# SuperBC.net
KiCad netlist of a schematic drawn in Altium Designer
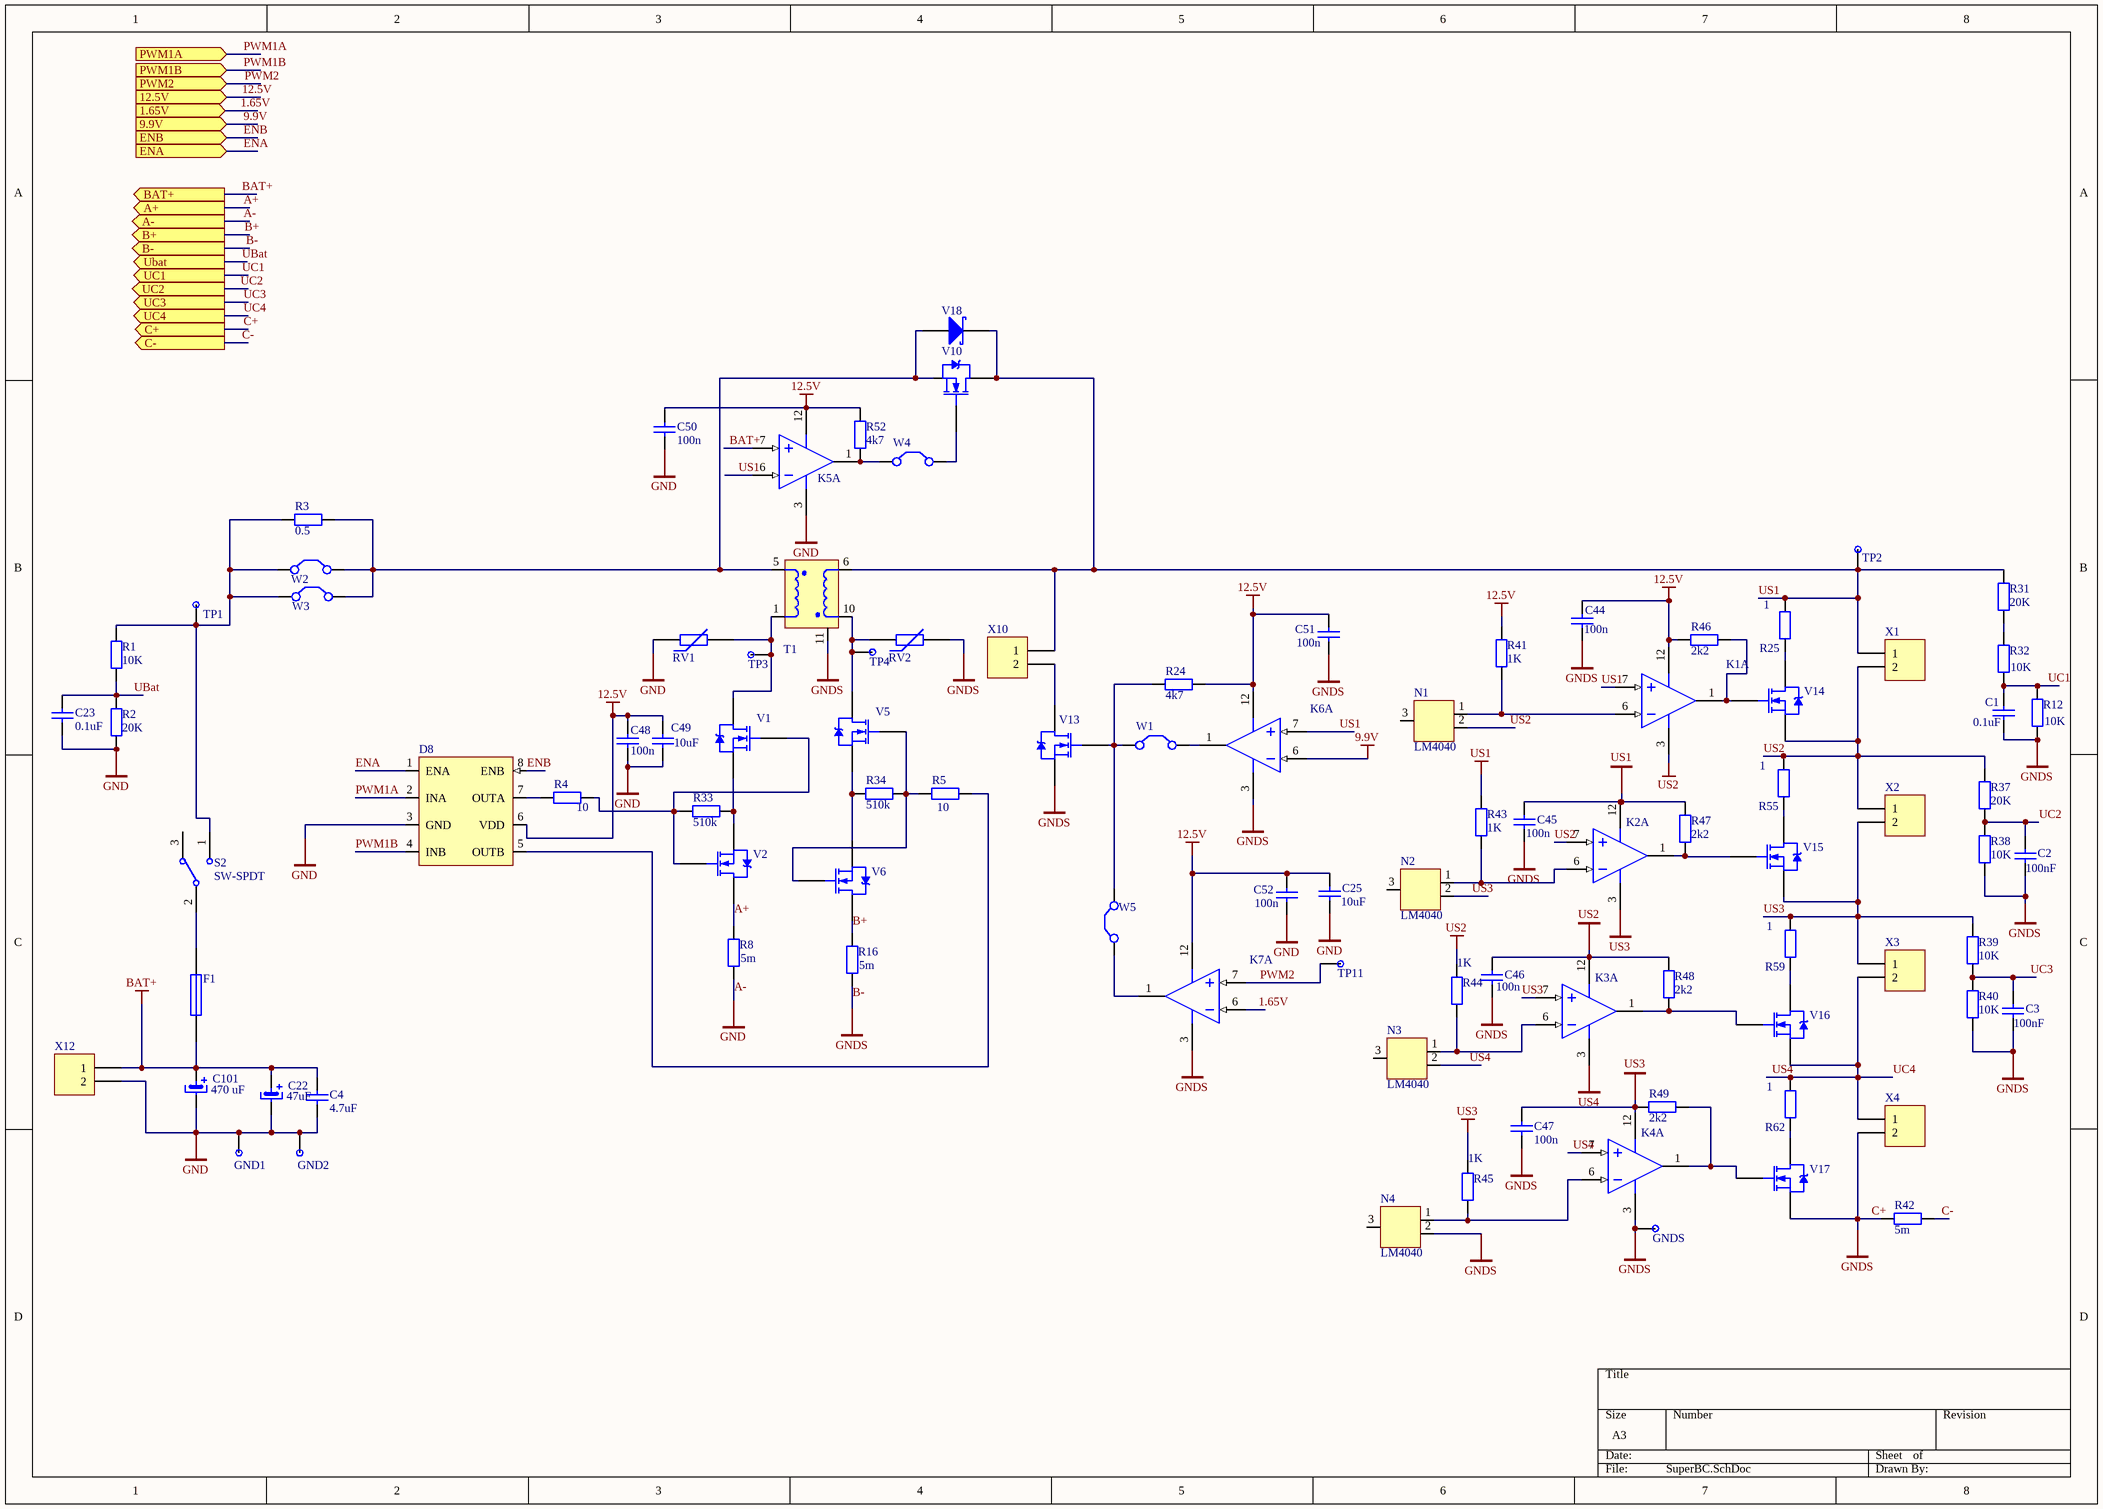
[diagram p0: SuperBC.SchDoc]

(export (version "E")
  (design (tool "Eeschema 10.0.6"))
  (components
    (comp (ref "C1")
      (value "0.1uF")
      (footprint "C1210_L")
      (description "Capacitor")
      (libsource (lib "Miscellaneous Devices") (part "Cap"))
    )
    (comp (ref "C2")
      (value "100nF")
      (footprint "C1210_L")
      (description "Capacitor")
      (fields (field (name "Comment") "0.1uF"))
      (libsource (lib "Miscellaneous Devices") (part "Cap"))
    )
    (comp (ref "C3")
      (value "100nF")
      (footprint "C1210_L")
      (description "Capacitor")
      (fields (field (name "Comment") "0.1uF"))
      (libsource (lib "Miscellaneous Devices") (part "Cap"))
    )
    (comp (ref "C4")
      (value "4.7uF")
      (footprint "C0805")
      (description "Capacitor")
      (libsource (lib "Miscellaneous Devices") (part "Cap"))
    )
    (comp (ref "C22")
      (value "47uF")
      (footprint "SMD_CAP_RAD_8X10.2")
      (libsource (lib "komponente") (part "elko"))
    )
    (comp (ref "C23")
      (value "0.1uF")
      (footprint "C1210_L")
      (description "Capacitor")
      (libsource (lib "Miscellaneous Devices") (part "Cap"))
    )
    (comp (ref "C25")
      (value "10uF")
      (footprint "C1210_L")
      (description "Capacitor")
      (libsource (lib "Miscellaneous Devices") (part "Cap"))
    )
    (comp (ref "C44")
      (value "100n")
      (footprint "C0805")
      (description "Capacitor")
      (libsource (lib "Miscellaneous Devices") (part "Cap"))
    )
    (comp (ref "C45")
      (value "100n")
      (footprint "C0805")
      (description "Capacitor")
      (libsource (lib "Miscellaneous Devices") (part "Cap"))
    )
    (comp (ref "C46")
      (value "100n")
      (footprint "C0805")
      (description "Capacitor")
      (libsource (lib "Miscellaneous Devices") (part "Cap"))
    )
    (comp (ref "C47")
      (value "100n")
      (footprint "C0805")
      (description "Capacitor")
      (libsource (lib "Miscellaneous Devices") (part "Cap"))
    )
    (comp (ref "C48")
      (value "100n")
      (footprint "C0805")
      (description "Capacitor")
      (libsource (lib "Miscellaneous Devices") (part "Cap"))
    )
    (comp (ref "C49")
      (value "10uF")
      (footprint "C1210_L")
      (description "Capacitor")
      (libsource (lib "Miscellaneous Devices") (part "Cap"))
    )
    (comp (ref "C50")
      (value "100n")
      (footprint "C0805")
      (description "Capacitor")
      (libsource (lib "Miscellaneous Devices") (part "Cap"))
    )
    (comp (ref "C51")
      (value "100n")
      (footprint "C0805")
      (description "Capacitor")
      (libsource (lib "Miscellaneous Devices") (part "Cap"))
    )
    (comp (ref "C52")
      (value "100n")
      (footprint "C0805")
      (description "Capacitor")
      (libsource (lib "Miscellaneous Devices") (part "Cap"))
    )
    (comp (ref "C101")
      (value "470 uF")
      (footprint "SMD_CAP_RAD_8X10.2")
      (libsource (lib "komponente") (part "elko"))
    )
    (comp (ref "D8")
      (value "driver_mosfet")
      (footprint "SOIC8")
      (libsource (lib "komponente") (part "driver_mosfet"))
    )
    (comp (ref "F1")
      (value "Fuse 1")
      (footprint "C1206")
      (description "Fuse")
      (libsource (lib "Miscellaneous Devices") (part "Fuse 1"))
    )
    (comp (ref "GND1") (value "*") (libsource (lib "komponente") (part "testpoint")))
    (comp (ref "GND2") (value "*") (libsource (lib "komponente") (part "testpoint")))
    (comp (ref "GNDS") (value "*") (libsource (lib "komponente") (part "testpoint")))
    (comp (ref "K1")
      (value "TLC3704QJ")
      (footprint "SOT-23")
      (description "Low Power Quad Differential Comparator")
      (libsource (lib "TI Analog Comparator") (part "LP2901D"))
    )
    (comp (ref "K2")
      (value "TLC3704QJ")
      (footprint "SOT-23")
      (description "Low Power Quad Differential Comparator")
      (libsource (lib "TI Analog Comparator") (part "LP2901D"))
    )
    (comp (ref "K3")
      (value "TLC3704QJ")
      (footprint "SOT-23")
      (description "Low Power Quad Differential Comparator")
      (libsource (lib "TI Analog Comparator") (part "LP2901D"))
    )
    (comp (ref "K4")
      (value "TLC3704QJ")
      (footprint "SOT-23")
      (description "Low Power Quad Differential Comparator")
      (libsource (lib "TI Analog Comparator") (part "LP2901D"))
    )
    (comp (ref "K5")
      (value "NCS2200")
      (footprint "SOT-23")
      (description "Low Power Quad Differential Comparator")
      (libsource (lib "TI Analog Comparator") (part "LP2901D"))
    )
    (comp (ref "K6")
      (value "TLC3704QJ")
      (footprint "SOT-23")
      (description "Low Power Quad Differential Comparator")
      (libsource (lib "TI Analog Comparator") (part "LP2901D"))
    )
    (comp (ref "K7")
      (value "TLC3704QJ")
      (footprint "SOT-23")
      (description "Low Power Quad Differential Comparator")
      (libsource (lib "TI Analog Comparator") (part "LP2901D"))
    )
    (comp (ref "N1")
      (value "LM4040")
      (footprint "SOT-23-ref_chip")
      (libsource (lib "komponente") (part "referentni chip"))
    )
    (comp (ref "N2")
      (value "LM4040")
      (footprint "SOT-23-ref_chip")
      (libsource (lib "komponente") (part "referentni chip"))
    )
    (comp (ref "N3")
      (value "LM4040")
      (footprint "SOT-23-ref_chip")
      (libsource (lib "komponente") (part "referentni chip"))
    )
    (comp (ref "N4")
      (value "LM4040")
      (footprint "SOT-23-ref_chip")
      (libsource (lib "komponente") (part "referentni chip"))
    )
    (comp (ref "R1")
      (value "10K")
      (footprint "C1210_L")
      (description "Resistor")
      (libsource (lib "Miscellaneous Devices") (part "Res2"))
    )
    (comp (ref "R2")
      (value "20K")
      (footprint "C1210_L")
      (description "Resistor")
      (libsource (lib "Miscellaneous Devices") (part "Res2"))
    )
    (comp (ref "R3")
      (value "0.5")
      (footprint "C2512")
      (description "Resistor")
      (libsource (lib "") (part "Res2_1"))
    )
    (comp (ref "R4")
      (value "10")
      (footprint "C0805")
      (description "Resistor")
      (libsource (lib "") (part "Res2_1"))
    )
    (comp (ref "R5")
      (value "10")
      (footprint "C0805")
      (description "Resistor")
      (libsource (lib "") (part "Res2_1"))
    )
    (comp (ref "R8")
      (value "5m")
      (footprint "otpornik R8, R16")
      (description "Resistor")
      (libsource (lib "Miscellaneous Devices") (part "Res2"))
    )
    (comp (ref "R12")
      (value "10K")
      (footprint "C1210_L")
      (description "Resistor")
      (libsource (lib "") (part "Res2_1"))
    )
    (comp (ref "R16")
      (value "5m")
      (footprint "otpornik R8, R16")
      (description "Resistor")
      (libsource (lib "Miscellaneous Devices") (part "Res2"))
    )
    (comp (ref "R24")
      (value "4k7")
      (footprint "C1206")
      (description "Resistor")
      (libsource (lib "") (part "Res2_1"))
    )
    (comp (ref "R25")
      (value "1")
      (footprint "F za 7W otpornik")
      (description "Resistor")
      (libsource (lib "Miscellaneous Devices") (part "Res2"))
    )
    (comp (ref "R31")
      (value "20K")
      (footprint "C1210_L")
      (description "Resistor")
      (libsource (lib "Miscellaneous Devices") (part "Res2"))
    )
    (comp (ref "R32")
      (value "10K")
      (footprint "C1210_L")
      (description "Resistor")
      (libsource (lib "") (part "Res2_1"))
    )
    (comp (ref "R33")
      (value "510k")
      (footprint "C1210_L")
      (description "Resistor")
      (libsource (lib "") (part "Res2_1"))
    )
    (comp (ref "R34")
      (value "510k")
      (footprint "C1210_L")
      (description "Resistor")
      (libsource (lib "") (part "Res2_1"))
    )
    (comp (ref "R37")
      (value "20K")
      (footprint "C1210_L")
      (description "Resistor")
      (libsource (lib "Miscellaneous Devices") (part "Res2"))
    )
    (comp (ref "R38")
      (value "10K")
      (footprint "C1210_L")
      (description "Resistor")
      (libsource (lib "Miscellaneous Devices") (part "Res2"))
    )
    (comp (ref "R39")
      (value "10K")
      (footprint "C1210_L")
      (description "Resistor")
      (libsource (lib "Miscellaneous Devices") (part "Res2"))
    )
    (comp (ref "R40")
      (value "10K")
      (footprint "C1210_L")
      (description "Resistor")
      (libsource (lib "Miscellaneous Devices") (part "Res2"))
    )
    (comp (ref "R41")
      (value "1K")
      (footprint "C1210_L")
      (description "Resistor")
      (libsource (lib "Miscellaneous Devices") (part "Res2"))
    )
    (comp (ref "R42")
      (value "5m")
      (footprint "otpornik R8, R16")
      (description "Resistor")
      (libsource (lib "") (part "Res2_2"))
    )
    (comp (ref "R43")
      (value "1K")
      (footprint "C1210_L")
      (description "Resistor")
      (libsource (lib "Miscellaneous Devices") (part "Res2"))
    )
    (comp (ref "R44")
      (value "1K")
      (footprint "C1210_L")
      (description "Resistor")
      (libsource (lib "Miscellaneous Devices") (part "Res2"))
    )
    (comp (ref "R45")
      (value "1K")
      (footprint "C1210_L")
      (description "Resistor")
      (libsource (lib "Miscellaneous Devices") (part "Res2"))
    )
    (comp (ref "R46")
      (value "2k2")
      (footprint "C1210_L")
      (description "Resistor")
      (libsource (lib "") (part "Res2_1"))
    )
    (comp (ref "R47")
      (value "2k2")
      (footprint "C1210_L")
      (description "Resistor")
      (libsource (lib "Miscellaneous Devices") (part "Res2"))
    )
    (comp (ref "R48")
      (value "2k2")
      (footprint "C1210_L")
      (description "Resistor")
      (libsource (lib "Miscellaneous Devices") (part "Res2"))
    )
    (comp (ref "R49")
      (value "2k2")
      (footprint "C1210_L")
      (description "Resistor")
      (libsource (lib "") (part "Res2_2"))
    )
    (comp (ref "R52")
      (value "4k7")
      (footprint "C1206")
      (description "Resistor")
      (libsource (lib "Miscellaneous Devices") (part "Res2"))
    )
    (comp (ref "R55")
      (value "1")
      (footprint "F za 7W otpornik")
      (description "Resistor")
      (libsource (lib "Miscellaneous Devices") (part "Res2"))
    )
    (comp (ref "R59")
      (value "1")
      (footprint "F za 7W otpornik")
      (description "Resistor")
      (libsource (lib "Miscellaneous Devices") (part "Res2"))
    )
    (comp (ref "R62")
      (value "1")
      (footprint "F za 7W otpornik")
      (description "Resistor")
      (libsource (lib "Miscellaneous Devices") (part "Res2"))
    )
    (comp (ref "RV1")
      (value "Res Varistor")
      (footprint "C1210_L")
      (description "Varistor (Voltage-Sensitive Resistor)")
      (libsource (lib "Miscellaneous Devices") (part "Res Varistor"))
    )
    (comp (ref "RV2")
      (value "Res Varistor")
      (footprint "C1210_L")
      (description "Varistor (Voltage-Sensitive Resistor)")
      (libsource (lib "Miscellaneous Devices") (part "Res Varistor"))
    )
    (comp (ref "S2")
      (value "SW-SPDT")
      (footprint "toggle_switch")
      (description "SPDT Subminiature Toggle Switch, Right Angle Mounting, Vertical Actuation")
      (libsource (lib "Miscellaneous Devices") (part "SW-SPDT"))
    )
    (comp (ref "T1")
      (value "transformator")
      (footprint "F za transformator")
      (libsource (lib "komponente") (part "transformator"))
    )
    (comp (ref "TP1") (value "*") (libsource (lib "komponente") (part "testpoint")))
    (comp (ref "TP2") (value "*") (libsource (lib "komponente") (part "testpoint")))
    (comp (ref "TP3") (value "*") (libsource (lib "komponente") (part "testpoint")))
    (comp (ref "TP4") (value "*") (libsource (lib "komponente") (part "testpoint")))
    (comp (ref "TP11") (value "*") (libsource (lib "komponente") (part "testpoint")))
    (comp (ref "V1")
      (value "NMOS-2")
      (footprint "SO-8L single_f")
      (description "N-Channel Power MOSFET")
      (libsource (lib "") (part "NMOS-2_1"))
    )
    (comp (ref "V2")
      (value "NMOS-2")
      (footprint "SO-8L single_f")
      (description "N-Channel Power MOSFET")
      (libsource (lib "") (part "NMOS-2_1"))
    )
    (comp (ref "V5")
      (value "NMOS-2")
      (footprint "SO-8L single_f")
      (description "N-Channel Power MOSFET")
      (libsource (lib "") (part "NMOS-2_1"))
    )
    (comp (ref "V6")
      (value "NMOS-2")
      (footprint "SO-8L single_f")
      (description "N-Channel Power MOSFET")
      (libsource (lib "") (part "NMOS-2_1"))
    )
    (comp (ref "V10")
      (value "MOSFET-N")
      (footprint "TO-252-3")
      (description "N-Channel Power MOSFET")
      (libsource (lib "Miscellaneous Devices") (part "NMOS-2"))
    )
    (comp (ref "V13")
      (value "MOSFET-N")
      (footprint "TO-252-3")
      (description "N-Channel Power MOSFET")
      (libsource (lib "Miscellaneous Devices") (part "NMOS-2"))
    )
    (comp (ref "V14")
      (value "NMOS-2")
      (footprint "SO-8L single_f")
      (description "N-Channel Power MOSFET")
      (libsource (lib "") (part "NMOS-2_1"))
    )
    (comp (ref "V15")
      (value "NMOS-2")
      (footprint "SO-8L single_f")
      (description "N-Channel Power MOSFET")
      (libsource (lib "") (part "NMOS-2_1"))
    )
    (comp (ref "V16")
      (value "NMOS-2")
      (footprint "SO-8L single_f")
      (description "N-Channel Power MOSFET")
      (libsource (lib "") (part "NMOS-2_1"))
    )
    (comp (ref "V17")
      (value "NMOS-2")
      (footprint "SO-8L single_f")
      (description "N-Channel Power MOSFET")
      (libsource (lib "") (part "NMOS-2_1"))
    )
    (comp (ref "V18")
      (value "Schottky Diode")
      (footprint "TO-220-AB")
      (libsource (lib "Miscellaneous Devices") (part "D Schottky"))
    )
    (comp (ref "W1")
      (value "Jumper")
      (footprint "HDR1X2")
      (description "Jumper Wire")
      (libsource (lib "Miscellaneous Devices") (part "Jumper"))
    )
    (comp (ref "W2")
      (value "Jumper 4.3A")
      (footprint "HDR1X2")
      (description "Jumper Wire")
      (libsource (lib "Miscellaneous Devices") (part "Jumper"))
    )
    (comp (ref "W3")
      (value "Jumper 4.3A")
      (footprint "HDR1X2")
      (description "Jumper Wire")
      (libsource (lib "Miscellaneous Devices") (part "Jumper"))
    )
    (comp (ref "W4")
      (value "Jumper")
      (footprint "HDR1X2")
      (description "Jumper Wire")
      (libsource (lib "Miscellaneous Devices") (part "Jumper"))
    )
    (comp (ref "W5")
      (value "Jumper")
      (footprint "HDR1X2")
      (description "Jumper Wire")
      (libsource (lib "Miscellaneous Devices") (part "Jumper"))
    )
    (comp (ref "X1")
      (value "Header 2")
      (footprint "F Header 1x2")
      (description "Header, 2-Pin")
      (libsource (lib "") (part "Header 2_1"))
    )
    (comp (ref "X2")
      (value "Header 2")
      (footprint "F Header 1x2")
      (description "Header, 2-Pin")
      (libsource (lib "") (part "Header 2_1"))
    )
    (comp (ref "X3")
      (value "Header 2")
      (footprint "F Header 1x2")
      (description "Header, 2-Pin")
      (libsource (lib "") (part "Header 2_1"))
    )
    (comp (ref "X4")
      (value "Header 2")
      (footprint "F Header 1x2")
      (description "Header, 2-Pin")
      (libsource (lib "") (part "Header 2_1"))
    )
    (comp (ref "X10")
      (value "Header 2")
      (footprint "F Header 1x2")
      (description "Header, 2-Pin")
      (libsource (lib "Miscellaneous Connectors") (part "Header 2"))
    )
    (comp (ref "X12")
      (value "Header 2")
      (footprint "F Header 1x2")
      (description "Header, 2-Pin")
      (libsource (lib "Miscellaneous Connectors") (part "Header 2"))
    )
  )
  (nets
    (net (code "1") (name "/1.65V") (class "Default")
      (node (ref "K7") (pin "6") (pinfunction "IN-_6") (pintype "input"))
    )
    (net (code "3") (name "/A+") (class "Default")
      (node (ref "R8") (pin "2") (pinfunction "2_2") (pintype "passive"))
      (node (ref "V2") (pin "2") (pinfunction "D_2") (pintype "passive"))
    )
    (net (code "4") (name "/B+") (class "Default")
      (node (ref "R16") (pin "2") (pinfunction "2_2") (pintype "passive"))
      (node (ref "V6") (pin "2") (pinfunction "D_2") (pintype "passive"))
    )
    (net (code "5") (name "/C-") (class "Default")
      (node (ref "R42") (pin "1") (pinfunction "1_1") (pintype "passive"))
    )
    (net (code "6") (name "/ENA") (class "Default")
      (node (ref "D8") (pin "1") (pinfunction "ENA_1") (pintype "bidirectional"))
    )
    (net (code "7") (name "/ENB") (class "Default")
      (node (ref "D8") (pin "8") (pinfunction "ENB_8") (pintype "input"))
    )
    (net (code "8") (name "/PWM1A") (class "Default")
      (node (ref "D8") (pin "2") (pinfunction "INA_2") (pintype "passive"))
    )
    (net (code "9") (name "/PWM1B") (class "Default")
      (node (ref "D8") (pin "4") (pinfunction "INB_4") (pintype "passive"))
    )
    (net (code "10") (name "/PWM2") (class "Default")
      (node (ref "K7") (pin "7") (pinfunction "IN+_7") (pintype "input"))
      (node (ref "TP11") (pin "1") (pinfunction "1_1") (pintype "passive"))
    )
    (net (code "11") (name "/UBat") (class "Default")
      (node (ref "C23") (pin "2") (pinfunction "2_2") (pintype "passive"))
      (node (ref "R1") (pin "1") (pinfunction "1_1") (pintype "passive"))
      (node (ref "R2") (pin "2") (pinfunction "2_2") (pintype "passive"))
    )
    (net (code "12") (name "/UC1") (class "Default")
      (node (ref "C1") (pin "2") (pinfunction "2_2") (pintype "passive"))
      (node (ref "R12") (pin "2") (pinfunction "2_2") (pintype "passive"))
      (node (ref "R32") (pin "1") (pinfunction "1_1") (pintype "passive"))
    )
    (net (code "13") (name "/UC2") (class "Default")
      (node (ref "C2") (pin "2") (pinfunction "2_2") (pintype "passive"))
      (node (ref "R37") (pin "1") (pinfunction "1_1") (pintype "passive"))
      (node (ref "R38") (pin "2") (pinfunction "2_2") (pintype "passive"))
    )
    (net (code "14") (name "/UC3") (class "Default")
      (node (ref "C3") (pin "2") (pinfunction "2_2") (pintype "passive"))
      (node (ref "R39") (pin "1") (pinfunction "1_1") (pintype "passive"))
      (node (ref "R40") (pin "2") (pinfunction "2_2") (pintype "passive"))
    )
    (net (code "15") (name "9.9V") (class "Default")
      (node (ref "K6") (pin "6") (pinfunction "IN-_6") (pintype "input"))
    )
    (net (code "16") (name "12.5V") (class "Default")
      (node (ref "C25") (pin "2") (pinfunction "2_2") (pintype "passive"))
      (node (ref "C44") (pin "2") (pinfunction "2_2") (pintype "passive"))
      (node (ref "C48") (pin "2") (pinfunction "2_2") (pintype "passive"))
      (node (ref "C49") (pin "2") (pinfunction "2_2") (pintype "passive"))
      (node (ref "C50") (pin "2") (pinfunction "2_2") (pintype "passive"))
      (node (ref "C51") (pin "2") (pinfunction "2_2") (pintype "passive"))
      (node (ref "C52") (pin "2") (pinfunction "2_2") (pintype "passive"))
      (node (ref "D8") (pin "6") (pinfunction "VDD_6") (pintype "passive"))
      (node (ref "K1") (pin "12") (pinfunction "V-_12") (pintype "passive"))
      (node (ref "K5") (pin "12") (pinfunction "V-_12") (pintype "passive"))
      (node (ref "K6") (pin "12") (pinfunction "V-_12") (pintype "passive"))
      (node (ref "K7") (pin "12") (pinfunction "V-_12") (pintype "passive"))
      (node (ref "R24") (pin "2") (pinfunction "2_2") (pintype "passive"))
      (node (ref "R41") (pin "2") (pinfunction "2_2") (pintype "passive"))
      (node (ref "R46") (pin "1") (pinfunction "1_1") (pintype "passive"))
      (node (ref "R52") (pin "2") (pinfunction "2_2") (pintype "passive"))
    )
    (net (code "17") (name "BAT+") (class "Default")
      (node (ref "C101") (pin "1") (pintype "passive"))
      (node (ref "C22") (pin "1") (pintype "passive"))
      (node (ref "C4") (pin "2") (pinfunction "2_2") (pintype "passive"))
      (node (ref "F1") (pin "1") (pinfunction "1_1") (pintype "passive"))
      (node (ref "K5") (pin "7") (pinfunction "IN+_7") (pintype "input"))
      (node (ref "X12") (pin "1") (pinfunction "1_1") (pintype "passive"))
    )
    (net (code "18") (name "GND") (class "Default")
      (node (ref "C101") (pin "2") (pinfunction "2_2") (pintype "passive"))
      (node (ref "C22") (pin "2") (pinfunction "2_2") (pintype "passive"))
      (node (ref "C23") (pin "1") (pinfunction "1_1") (pintype "passive"))
      (node (ref "C25") (pin "1") (pinfunction "1_1") (pintype "passive"))
      (node (ref "C4") (pin "1") (pinfunction "1_1") (pintype "passive"))
      (node (ref "C48") (pin "1") (pinfunction "1_1") (pintype "passive"))
      (node (ref "C49") (pin "1") (pinfunction "1_1") (pintype "passive"))
      (node (ref "C50") (pin "1") (pinfunction "1_1") (pintype "passive"))
      (node (ref "C52") (pin "1") (pinfunction "1_1") (pintype "passive"))
      (node (ref "D8") (pin "3") (pinfunction "GND_3") (pintype "bidirectional"))
      (node (ref "GND1") (pin "1") (pinfunction "1_1") (pintype "passive"))
      (node (ref "GND2") (pin "1") (pinfunction "1_1") (pintype "passive"))
      (node (ref "K5") (pin "3") (pinfunction "V+_3") (pintype "passive"))
      (node (ref "R2") (pin "1") (pinfunction "1_1") (pintype "passive"))
      (node (ref "R8") (pin "1") (pinfunction "1_1") (pintype "passive"))
      (node (ref "RV1") (pin "1") (pinfunction "1_1") (pintype "passive"))
      (node (ref "X12") (pin "2") (pinfunction "2_2") (pintype "passive"))
    )
    (net (code "19") (name "GNDS") (class "Default")
      (node (ref "C1") (pin "1") (pinfunction "1_1") (pintype "passive"))
      (node (ref "C2") (pin "1") (pinfunction "1_1") (pintype "passive"))
      (node (ref "C3") (pin "1") (pinfunction "1_1") (pintype "passive"))
      (node (ref "C44") (pin "1") (pinfunction "1_1") (pintype "passive"))
      (node (ref "C45") (pin "1") (pinfunction "1_1") (pintype "passive"))
      (node (ref "C46") (pin "1") (pinfunction "1_1") (pintype "passive"))
      (node (ref "C47") (pin "1") (pinfunction "1_1") (pintype "passive"))
      (node (ref "C51") (pin "1") (pinfunction "1_1") (pintype "passive"))
      (node (ref "GNDS") (pin "1") (pinfunction "1_1") (pintype "passive"))
      (node (ref "K4") (pin "3") (pinfunction "V+_3") (pintype "passive"))
      (node (ref "K6") (pin "3") (pinfunction "V+_3") (pintype "passive"))
      (node (ref "K7") (pin "3") (pinfunction "V+_3") (pintype "passive"))
      (node (ref "N4") (pin "2") (pinfunction "2_2") (pintype "passive"))
      (node (ref "R12") (pin "1") (pinfunction "1_1") (pintype "passive"))
      (node (ref "R16") (pin "1") (pinfunction "1_1") (pintype "passive"))
      (node (ref "R38") (pin "1") (pinfunction "1_1") (pintype "passive"))
      (node (ref "R40") (pin "1") (pinfunction "1_1") (pintype "passive"))
      (node (ref "R42") (pin "2") (pinfunction "2_2") (pintype "passive"))
      (node (ref "RV2") (pin "2") (pinfunction "2_2") (pintype "passive"))
      (node (ref "T1") (pin "11") (pinfunction "11_11") (pintype "passive"))
      (node (ref "V13") (pin "2") (pinfunction "S_2") (pintype "passive"))
      (node (ref "V17") (pin "3") (pinfunction "S_3") (pintype "passive"))
      (node (ref "X4") (pin "2") (pinfunction "2_2") (pintype "passive"))
    )
    (net (code "20") (name "Net-(D8-OUTA)") (class "Default")
      (node (ref "D8") (pin "7") (pinfunction "OUTA_7") (pintype "passive"))
      (node (ref "R4") (pin "1") (pinfunction "1_1") (pintype "passive"))
    )
    (net (code "21") (name "Net-(D8-OUTB)") (class "Default")
      (node (ref "D8") (pin "5") (pinfunction "OUTB_5") (pintype "passive"))
      (node (ref "R5") (pin "2") (pinfunction "2_2") (pintype "passive"))
    )
    (net (code "22") (name "Net-(F1-Pad2)") (class "Default")
      (node (ref "F1") (pin "2") (pinfunction "2_2") (pintype "passive"))
      (node (ref "S2") (pin "2") (pinfunction "2_2") (pintype "passive"))
    )
    (net (code "23") (name "Net-(K1A-IN-)") (class "Default")
      (node (ref "K1") (pin "6") (pinfunction "IN-_6") (pintype "input"))
      (node (ref "N1") (pin "1") (pinfunction "1_1") (pintype "bidirectional"))
      (node (ref "R41") (pin "1") (pinfunction "1_1") (pintype "passive"))
    )
    (net (code "24") (name "Net-(K1A-OUT)") (class "Default")
      (node (ref "K1") (pin "1") (pinfunction "OUT_1") (pintype "open_collector"))
      (node (ref "R46") (pin "2") (pinfunction "2_2") (pintype "passive"))
      (node (ref "V14") (pin "1") (pinfunction "G_1") (pintype "passive"))
    )
    (net (code "25") (name "Net-(K2A-IN-)") (class "Default")
      (node (ref "K2") (pin "6") (pinfunction "IN-_6") (pintype "input"))
      (node (ref "N2") (pin "1") (pinfunction "1_1") (pintype "bidirectional"))
      (node (ref "R43") (pin "1") (pinfunction "1_1") (pintype "passive"))
    )
    (net (code "26") (name "Net-(K2A-OUT)") (class "Default")
      (node (ref "K2") (pin "1") (pinfunction "OUT_1") (pintype "open_collector"))
      (node (ref "R47") (pin "1") (pinfunction "1_1") (pintype "passive"))
      (node (ref "V15") (pin "1") (pinfunction "G_1") (pintype "passive"))
    )
    (net (code "27") (name "Net-(K3A-IN-)") (class "Default")
      (node (ref "K3") (pin "6") (pinfunction "IN-_6") (pintype "input"))
      (node (ref "N3") (pin "1") (pinfunction "1_1") (pintype "bidirectional"))
      (node (ref "R44") (pin "1") (pinfunction "1_1") (pintype "passive"))
    )
    (net (code "28") (name "Net-(K3A-OUT)") (class "Default")
      (node (ref "K3") (pin "1") (pinfunction "OUT_1") (pintype "open_collector"))
      (node (ref "R48") (pin "1") (pinfunction "1_1") (pintype "passive"))
      (node (ref "V16") (pin "1") (pinfunction "G_1") (pintype "passive"))
    )
    (net (code "29") (name "Net-(K4A-IN-)") (class "Default")
      (node (ref "K4") (pin "6") (pinfunction "IN-_6") (pintype "input"))
      (node (ref "N4") (pin "1") (pinfunction "1_1") (pintype "bidirectional"))
      (node (ref "R45") (pin "1") (pinfunction "1_1") (pintype "passive"))
    )
    (net (code "30") (name "Net-(K4A-OUT)") (class "Default")
      (node (ref "K4") (pin "1") (pinfunction "OUT_1") (pintype "open_collector"))
      (node (ref "R49") (pin "1") (pinfunction "1_1") (pintype "passive"))
      (node (ref "V17") (pin "1") (pinfunction "G_1") (pintype "passive"))
    )
    (net (code "31") (name "Net-(K5A-OUT)") (class "Default")
      (node (ref "K5") (pin "1") (pinfunction "OUT_1") (pintype "open_collector"))
      (node (ref "R52") (pin "1") (pinfunction "1_1") (pintype "passive"))
      (node (ref "W4") (pin "1") (pinfunction "C1_1") (pintype "passive"))
    )
    (net (code "32") (name "Net-(K6A-OUT)") (class "Default")
      (node (ref "K6") (pin "1") (pinfunction "OUT_1") (pintype "open_collector"))
      (node (ref "W1") (pin "2") (pinfunction "C2_2") (pintype "passive"))
    )
    (net (code "33") (name "Net-(K7A-OUT)") (class "Default")
      (node (ref "K7") (pin "1") (pinfunction "OUT_1") (pintype "open_collector"))
      (node (ref "W5") (pin "1") (pinfunction "C1_1") (pintype "passive"))
    )
    (net (code "34") (name "Net-(R31-Pad1)") (class "Default")
      (node (ref "R31") (pin "1") (pinfunction "1_1") (pintype "passive"))
      (node (ref "R32") (pin "2") (pinfunction "2_2") (pintype "passive"))
    )
    (net (code "35") (name "Net-(V1-D)") (class "Default")
      (node (ref "RV1") (pin "2") (pinfunction "2_2") (pintype "passive"))
      (node (ref "T1") (pin "1") (pinfunction "1_1") (pintype "passive"))
      (node (ref "TP3") (pin "1") (pinfunction "1_1") (pintype "passive"))
      (node (ref "V1") (pin "2") (pinfunction "D_2") (pintype "passive"))
    )
    (net (code "36") (name "Net-(V1-G)") (class "Default")
      (node (ref "R33") (pin "1") (pinfunction "1_1") (pintype "passive"))
      (node (ref "R4") (pin "2") (pinfunction "2_2") (pintype "passive"))
      (node (ref "V1") (pin "1") (pinfunction "G_1") (pintype "passive"))
      (node (ref "V2") (pin "1") (pinfunction "G_1") (pintype "passive"))
    )
    (net (code "37") (name "Net-(V1-S)_1") (class "Default")
      (node (ref "R33") (pin "2") (pinfunction "2_2") (pintype "passive"))
      (node (ref "V1") (pin "3") (pinfunction "S_3") (pintype "passive"))
      (node (ref "V2") (pin "3") (pinfunction "S_3") (pintype "passive"))
    )
    (net (code "38") (name "Net-(V5-D)") (class "Default")
      (node (ref "RV2") (pin "1") (pinfunction "1_1") (pintype "passive"))
      (node (ref "T1") (pin "10") (pinfunction "10_10") (pintype "passive"))
      (node (ref "TP4") (pin "1") (pinfunction "1_1") (pintype "passive"))
      (node (ref "V5") (pin "2") (pinfunction "D_2") (pintype "passive"))
    )
    (net (code "39") (name "Net-(V5-G)") (class "Default")
      (node (ref "R34") (pin "2") (pinfunction "2_2") (pintype "passive"))
      (node (ref "R5") (pin "1") (pinfunction "1_1") (pintype "passive"))
      (node (ref "V5") (pin "1") (pinfunction "G_1") (pintype "passive"))
      (node (ref "V6") (pin "1") (pinfunction "G_1") (pintype "passive"))
    )
    (net (code "40") (name "Net-(V5-S)_1") (class "Default")
      (node (ref "R34") (pin "1") (pinfunction "1_1") (pintype "passive"))
      (node (ref "V5") (pin "3") (pinfunction "S_3") (pintype "passive"))
      (node (ref "V6") (pin "3") (pinfunction "S_3") (pintype "passive"))
    )
    (net (code "41") (name "Net-(V10-G)") (class "Default")
      (node (ref "V10") (pin "1") (pinfunction "G_1") (pintype "passive"))
      (node (ref "W4") (pin "2") (pinfunction "C2_2") (pintype "passive"))
    )
    (net (code "42") (name "Net-(V10-S)") (class "Default")
      (node (ref "R3") (pin "2") (pinfunction "2_2") (pintype "passive"))
      (node (ref "T1") (pin "5") (pinfunction "5_5") (pintype "passive"))
      (node (ref "V10") (pin "2") (pinfunction "S_2") (pintype "passive"))
      (node (ref "V18") (pin "2") (pinfunction "K_2") (pintype "passive"))
      (node (ref "W2") (pin "2") (pinfunction "C2_2") (pintype "passive"))
      (node (ref "W3") (pin "2") (pinfunction "C2_2") (pintype "passive"))
    )
    (net (code "43") (name "Net-(V13-D)") (class "Default")
      (node (ref "V13") (pin "3") (pinfunction "D_3") (pintype "passive"))
      (node (ref "X10") (pin "2") (pinfunction "2_2") (pintype "passive"))
    )
    (net (code "44") (name "Net-(V13-G)") (class "Default")
      (node (ref "R24") (pin "1") (pinfunction "1_1") (pintype "passive"))
      (node (ref "V13") (pin "1") (pinfunction "G_1") (pintype "passive"))
      (node (ref "W1") (pin "1") (pinfunction "C1_1") (pintype "passive"))
      (node (ref "W5") (pin "2") (pinfunction "C2_2") (pintype "passive"))
    )
    (net (code "45") (name "Net-(V14-D)") (class "Default")
      (node (ref "R25") (pin "1") (pinfunction "1_1") (pintype "passive"))
      (node (ref "V14") (pin "2") (pinfunction "D_2") (pintype "passive"))
    )
    (net (code "46") (name "Net-(V15-D)") (class "Default")
      (node (ref "R55") (pin "1") (pinfunction "1_1") (pintype "passive"))
      (node (ref "V15") (pin "2") (pinfunction "D_2") (pintype "passive"))
    )
    (net (code "47") (name "Net-(V16-D)") (class "Default")
      (node (ref "R59") (pin "1") (pinfunction "1_1") (pintype "passive"))
      (node (ref "V16") (pin "2") (pinfunction "D_2") (pintype "passive"))
    )
    (net (code "48") (name "Net-(V17-D)") (class "Default")
      (node (ref "R62") (pin "1") (pinfunction "1_1") (pintype "passive"))
      (node (ref "V17") (pin "2") (pinfunction "D_2") (pintype "passive"))
    )
    (net (code "49") (name "Net-(W2-C1)") (class "Default")
      (node (ref "R1") (pin "2") (pinfunction "2_2") (pintype "passive"))
      (node (ref "R3") (pin "1") (pinfunction "1_1") (pintype "passive"))
      (node (ref "S2") (pin "1") (pinfunction "1_1") (pintype "passive"))
      (node (ref "TP1") (pin "1") (pinfunction "1_1") (pintype "passive"))
      (node (ref "W2") (pin "1") (pinfunction "C1_1") (pintype "passive"))
      (node (ref "W3") (pin "1") (pinfunction "C1_1") (pintype "passive"))
    )
    (net (code "50") (name "US1") (class "Default")
      (node (ref "C45") (pin "2") (pinfunction "2_2") (pintype "passive"))
      (node (ref "K1") (pin "7") (pinfunction "IN+_7") (pintype "input"))
      (node (ref "K2") (pin "12") (pinfunction "V-_12") (pintype "passive"))
      (node (ref "K5") (pin "6") (pinfunction "IN-_6") (pintype "input"))
      (node (ref "K6") (pin "7") (pinfunction "IN+_7") (pintype "input"))
      (node (ref "R25") (pin "2") (pinfunction "2_2") (pintype "passive"))
      (node (ref "R31") (pin "2") (pinfunction "2_2") (pintype "passive"))
      (node (ref "R43") (pin "2") (pinfunction "2_2") (pintype "passive"))
      (node (ref "R47") (pin "2") (pinfunction "2_2") (pintype "passive"))
      (node (ref "T1") (pin "6") (pinfunction "6_6") (pintype "passive"))
      (node (ref "TP2") (pin "1") (pinfunction "1_1") (pintype "passive"))
      (node (ref "V10") (pin "3") (pinfunction "D_3") (pintype "passive"))
      (node (ref "V18") (pin "1") (pinfunction "A_1") (pintype "passive"))
      (node (ref "X1") (pin "1") (pinfunction "1_1") (pintype "passive"))
      (node (ref "X10") (pin "1") (pinfunction "1_1") (pintype "passive"))
    )
    (net (code "51") (name "US2") (class "Default")
      (node (ref "C46") (pin "2") (pinfunction "2_2") (pintype "passive"))
      (node (ref "K1") (pin "3") (pinfunction "V+_3") (pintype "passive"))
      (node (ref "K2") (pin "7") (pinfunction "IN+_7") (pintype "input"))
      (node (ref "K3") (pin "12") (pinfunction "V-_12") (pintype "passive"))
      (node (ref "N1") (pin "2") (pinfunction "2_2") (pintype "passive"))
      (node (ref "R37") (pin "2") (pinfunction "2_2") (pintype "passive"))
      (node (ref "R44") (pin "2") (pinfunction "2_2") (pintype "passive"))
      (node (ref "R48") (pin "2") (pinfunction "2_2") (pintype "passive"))
      (node (ref "R55") (pin "2") (pinfunction "2_2") (pintype "passive"))
      (node (ref "V14") (pin "3") (pinfunction "S_3") (pintype "passive"))
      (node (ref "X1") (pin "2") (pinfunction "2_2") (pintype "passive"))
      (node (ref "X2") (pin "1") (pinfunction "1_1") (pintype "passive"))
    )
    (net (code "52") (name "US3") (class "Default")
      (node (ref "C47") (pin "2") (pinfunction "2_2") (pintype "passive"))
      (node (ref "K2") (pin "3") (pinfunction "V+_3") (pintype "passive"))
      (node (ref "K3") (pin "7") (pinfunction "IN+_7") (pintype "input"))
      (node (ref "K4") (pin "12") (pinfunction "V-_12") (pintype "passive"))
      (node (ref "N2") (pin "2") (pinfunction "2_2") (pintype "passive"))
      (node (ref "R39") (pin "2") (pinfunction "2_2") (pintype "passive"))
      (node (ref "R45") (pin "2") (pinfunction "2_2") (pintype "passive"))
      (node (ref "R49") (pin "2") (pinfunction "2_2") (pintype "passive"))
      (node (ref "R59") (pin "2") (pinfunction "2_2") (pintype "passive"))
      (node (ref "V15") (pin "3") (pinfunction "S_3") (pintype "passive"))
      (node (ref "X2") (pin "2") (pinfunction "2_2") (pintype "passive"))
      (node (ref "X3") (pin "1") (pinfunction "1_1") (pintype "passive"))
    )
    (net (code "53") (name "US4") (class "Default")
      (node (ref "K3") (pin "3") (pinfunction "V+_3") (pintype "passive"))
      (node (ref "K4") (pin "7") (pinfunction "IN+_7") (pintype "input"))
      (node (ref "N3") (pin "2") (pinfunction "2_2") (pintype "passive"))
      (node (ref "R62") (pin "2") (pinfunction "2_2") (pintype "passive"))
      (node (ref "V16") (pin "3") (pinfunction "S_3") (pintype "passive"))
      (node (ref "X3") (pin "2") (pinfunction "2_2") (pintype "passive"))
      (node (ref "X4") (pin "1") (pinfunction "1_1") (pintype "passive"))
    )
    (net (code "54") (name "unconnected-(N1-Pad3)") (class "Default")
      (node (ref "N1") (pin "3") (pinfunction "3_3") (pintype "passive"))
    )
    (net (code "55") (name "unconnected-(N2-Pad3)") (class "Default")
      (node (ref "N2") (pin "3") (pinfunction "3_3") (pintype "passive"))
    )
    (net (code "56") (name "unconnected-(N3-Pad3)") (class "Default")
      (node (ref "N3") (pin "3") (pinfunction "3_3") (pintype "passive"))
    )
    (net (code "57") (name "unconnected-(N4-Pad3)") (class "Default")
      (node (ref "N4") (pin "3") (pinfunction "3_3") (pintype "passive"))
    )
    (net (code "58") (name "unconnected-(S2-Pad3)") (class "Default")
      (node (ref "S2") (pin "3") (pinfunction "3_3") (pintype "passive"))
    )
    (net (code "59") (name "unconnected-(V1-S-Pad3)") (class "Default")
      (node (ref "V1") (pin "3") (pinfunction "S_3") (pintype "passive"))
    )
    (net (code "60") (name "unconnected-(V1-S-Pad3)_2") (class "Default")
      (node (ref "V1") (pin "3") (pinfunction "S_3") (pintype "passive"))
    )
    (net (code "61") (name "unconnected-(V2-S-Pad3)") (class "Default")
      (node (ref "V2") (pin "3") (pinfunction "S_3") (pintype "passive"))
    )
    (net (code "62") (name "unconnected-(V2-S-Pad3)_1") (class "Default")
      (node (ref "V2") (pin "3") (pinfunction "S_3") (pintype "passive"))
    )
    (net (code "63") (name "unconnected-(V5-S-Pad3)") (class "Default")
      (node (ref "V5") (pin "3") (pinfunction "S_3") (pintype "passive"))
    )
    (net (code "64") (name "unconnected-(V5-S-Pad3)_2") (class "Default")
      (node (ref "V5") (pin "3") (pinfunction "S_3") (pintype "passive"))
    )
    (net (code "65") (name "unconnected-(V6-S-Pad3)") (class "Default")
      (node (ref "V6") (pin "3") (pinfunction "S_3") (pintype "passive"))
    )
    (net (code "66") (name "unconnected-(V6-S-Pad3)_1") (class "Default")
      (node (ref "V6") (pin "3") (pinfunction "S_3") (pintype "passive"))
    )
    (net (code "67") (name "unconnected-(V14-S-Pad3)") (class "Default")
      (node (ref "V14") (pin "3") (pinfunction "S_3") (pintype "passive"))
    )
    (net (code "68") (name "unconnected-(V14-S-Pad3)_1") (class "Default")
      (node (ref "V14") (pin "3") (pinfunction "S_3") (pintype "passive"))
    )
    (net (code "69") (name "unconnected-(V15-S-Pad3)") (class "Default")
      (node (ref "V15") (pin "3") (pinfunction "S_3") (pintype "passive"))
    )
    (net (code "70") (name "unconnected-(V15-S-Pad3)_1") (class "Default")
      (node (ref "V15") (pin "3") (pinfunction "S_3") (pintype "passive"))
    )
    (net (code "71") (name "unconnected-(V16-S-Pad3)") (class "Default")
      (node (ref "V16") (pin "3") (pinfunction "S_3") (pintype "passive"))
    )
    (net (code "72") (name "unconnected-(V16-S-Pad3)_1") (class "Default")
      (node (ref "V16") (pin "3") (pinfunction "S_3") (pintype "passive"))
    )
    (net (code "73") (name "unconnected-(V17-S-Pad3)") (class "Default")
      (node (ref "V17") (pin "3") (pinfunction "S_3") (pintype "passive"))
    )
    (net (code "74") (name "unconnected-(V17-S-Pad3)_1") (class "Default")
      (node (ref "V17") (pin "3") (pinfunction "S_3") (pintype "passive"))
    )
  )
)
